# Dyn_MicSheet.net
KiCad netlist of a schematic drawn in Altium Designer
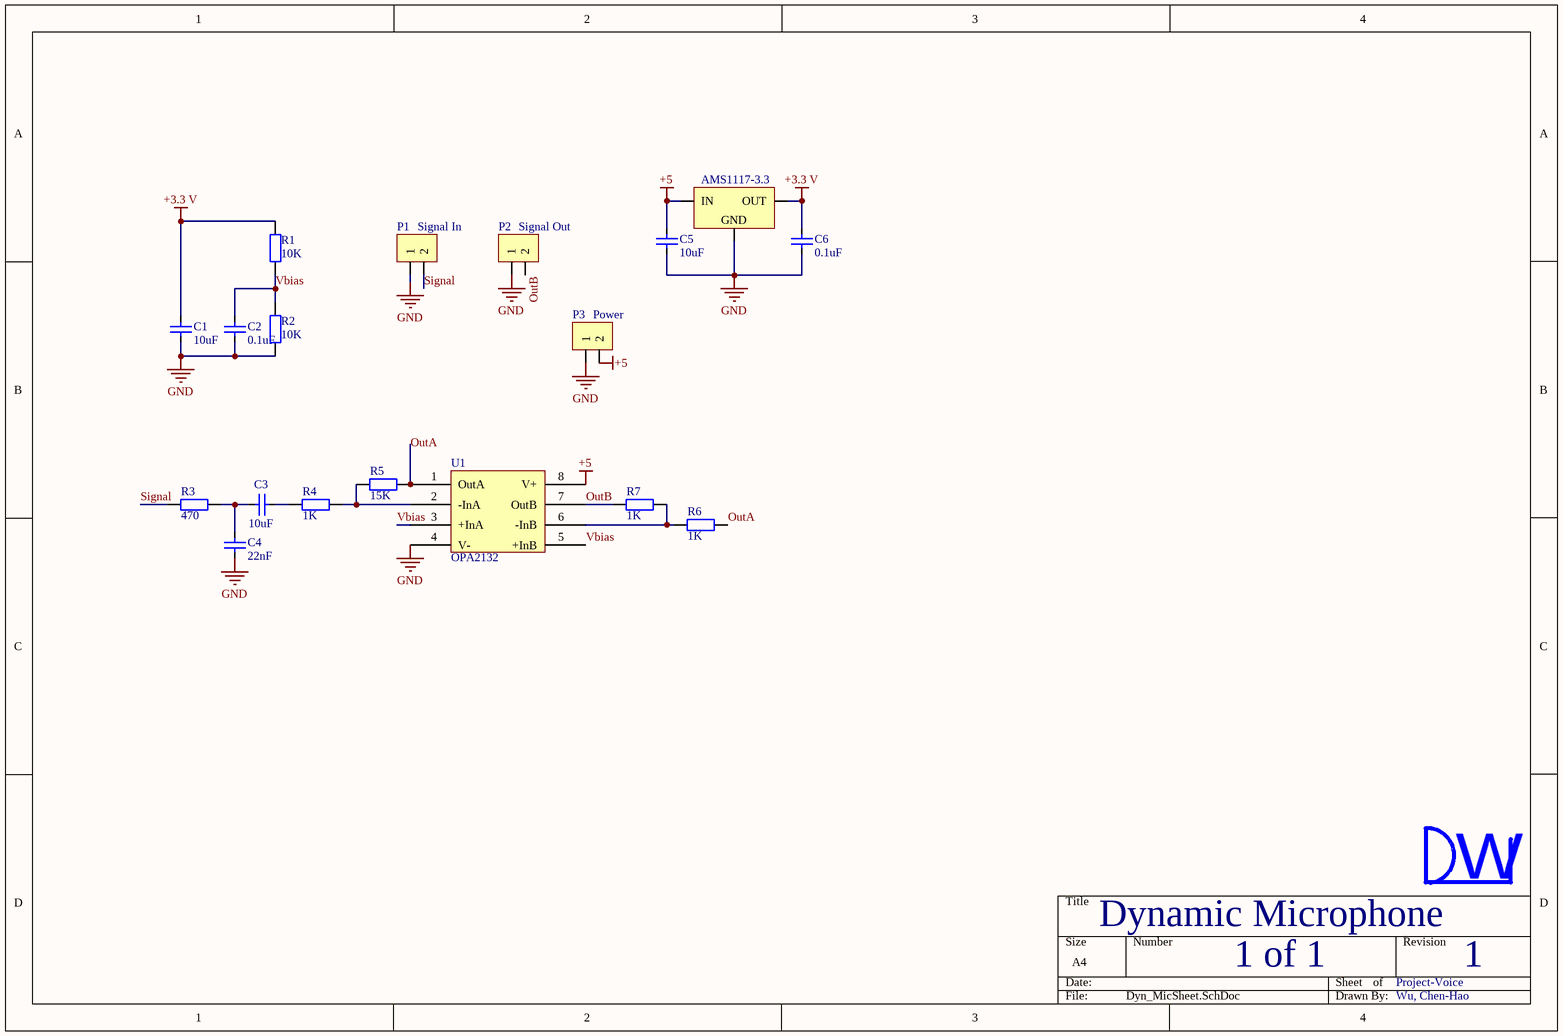
[diagram p0: Dyn_MicSheet.SchDoc]

(export (version "E")
  (design (tool "Eeschema 10.0.6"))
  (components
    (comp (ref "*") (value "DHW_MARK") (libsource (lib "SCH_Mark") (part "DHW_MARK")))
    (comp (ref "AMS1")
      (value "AMS1117-3.3")
      (footprint "PCB_IC:SOT223")
      (description "Power")
      (libsource (lib "SCH_IC") (part "AMS1117"))
    )
    (comp (ref "C1")
      (value "10uF")
      (footprint "PCB_Passive:CAP_0603")
      (description "Capacitor")
      (fields (field (name "Comment") "Cap_0603"))
      (libsource (lib "SCH_Passive") (part "Cap_0603"))
    )
    (comp (ref "C2")
      (value "0.1uF")
      (footprint "PCB_Passive:CAP_0603")
      (description "Capacitor")
      (fields (field (name "Comment") "Cap_0603"))
      (libsource (lib "SCH_Passive") (part "Cap_0603"))
    )
    (comp (ref "C3")
      (value "10uF")
      (footprint "PCB_Passive:CAP_0603")
      (description "Capacitor")
      (fields (field (name "Comment") "Cap_0603"))
      (libsource (lib "SCH_Passive") (part "Cap_0603"))
    )
    (comp (ref "C4")
      (value "22nF")
      (footprint "PCB_Passive:CAP_0603")
      (description "Capacitor")
      (fields (field (name "Comment") "Cap_0603"))
      (libsource (lib "SCH_Passive") (part "Cap_0603"))
    )
    (comp (ref "C5")
      (value "10uF")
      (footprint "PCB_Passive:CAP_0603")
      (description "Capacitor")
      (fields (field (name "Comment") "Cap_0603"))
      (libsource (lib "SCH_Passive") (part "Cap_0603"))
    )
    (comp (ref "C6")
      (value "0.1uF")
      (footprint "PCB_Passive:CAP_0603")
      (description "Capacitor")
      (fields (field (name "Comment") "Cap_0603"))
      (libsource (lib "SCH_Passive") (part "Cap_0603"))
    )
    (comp (ref "P1")
      (value "Signal In")
      (footprint "PCB_Connector:HDR1X2_180_2.54")
      (description "Header")
      (libsource (lib "SCH_Connector") (part "HDR1X2_180_2.54"))
    )
    (comp (ref "P2")
      (value "Signal Out")
      (footprint "PCB_Connector:HDR1X2_180_2.54")
      (description "Header")
      (libsource (lib "SCH_Connector") (part "HDR1X2_180_2.54"))
    )
    (comp (ref "P3")
      (value "Power")
      (footprint "PCB_Connector:HDR1X2_180_2.54")
      (description "Header")
      (libsource (lib "SCH_Connector") (part "HDR1X2_180_2.54"))
    )
    (comp (ref "R1")
      (value "10K")
      (footprint "PCB_Passive:RES_0603")
      (description "Resistor")
      (fields (field (name "Comment") "Res_0603"))
      (libsource (lib "") (part "Res_0603_1"))
    )
    (comp (ref "R2")
      (value "10K")
      (footprint "PCB_Passive:RES_0603")
      (description "Resistor")
      (fields (field (name "Comment") "Res_0603"))
      (libsource (lib "") (part "Res_0603_1"))
    )
    (comp (ref "R3")
      (value "470")
      (footprint "PCB_Passive:RES_0603")
      (description "Resistor")
      (fields (field (name "Comment") "Res_0603"))
      (libsource (lib "SCH_Passive") (part "Res_0603"))
    )
    (comp (ref "R4")
      (value "1K")
      (footprint "PCB_Passive:RES_0603")
      (description "Resistor")
      (fields (field (name "Comment") "Res_0603"))
      (libsource (lib "SCH_Passive") (part "Res_0603"))
    )
    (comp (ref "R5")
      (value "15K")
      (footprint "PCB_Passive:RES_0603")
      (description "Resistor")
      (fields (field (name "Comment") "Res_0603"))
      (libsource (lib "SCH_Passive") (part "Res_0603"))
    )
    (comp (ref "R6")
      (value "1K")
      (footprint "PCB_Passive:RES_0603")
      (description "Resistor")
      (fields (field (name "Comment") "Res_0603"))
      (libsource (lib "SCH_Passive") (part "Res_0603"))
    )
    (comp (ref "R7")
      (value "1K")
      (footprint "PCB_Passive:RES_0603")
      (description "Resistor")
      (fields (field (name "Comment") "Res_0603"))
      (libsource (lib "SCH_Passive") (part "Res_0603"))
    )
    (comp (ref "U1")
      (value "OPA2132")
      (footprint "DIP_8")
      (description "TI BB OPA2132 - 2 op amps IC")
      (libsource (lib "SCH_IC") (part "OPA2132"))
    )
  )
  (nets
    (net (code "1") (name "+3.3 V") (class "Default")
      (node (ref "AMS1") (pin "2") (pinfunction "OUT_2") (pintype "power_in"))
      (node (ref "C1") (pin "2") (pinfunction "2_2") (pintype "passive"))
      (node (ref "C6") (pin "2") (pinfunction "2_2") (pintype "passive"))
      (node (ref "R1") (pin "2") (pinfunction "2_2") (pintype "passive"))
    )
    (net (code "2") (name "+5") (class "Default")
      (node (ref "AMS1") (pin "3") (pinfunction "IN_3") (pintype "power_in"))
      (node (ref "C5") (pin "2") (pinfunction "2_2") (pintype "passive"))
      (node (ref "P3") (pin "2") (pinfunction "2_2") (pintype "passive"))
      (node (ref "U1") (pin "8") (pinfunction "V+_8") (pintype "passive"))
    )
    (net (code "3") (name "/OutA") (class "Default")
      (node (ref "R5") (pin "1") (pinfunction "1_1") (pintype "passive"))
      (node (ref "R6") (pin "1") (pinfunction "1_1") (pintype "passive"))
      (node (ref "U1") (pin "1") (pinfunction "OutA_1") (pintype "passive"))
    )
    (net (code "4") (name "/OutB") (class "Default")
      (node (ref "P2") (pin "2") (pinfunction "2_2") (pintype "passive"))
      (node (ref "R7") (pin "2") (pinfunction "2_2") (pintype "passive"))
      (node (ref "U1") (pin "7") (pinfunction "OutB_7") (pintype "passive"))
    )
    (net (code "5") (name "/Signal") (class "Default")
      (node (ref "P1") (pin "2") (pinfunction "2_2") (pintype "passive"))
      (node (ref "R3") (pin "2") (pinfunction "2_2") (pintype "passive"))
    )
    (net (code "6") (name "/Vbias") (class "Default")
      (node (ref "C2") (pin "2") (pinfunction "2_2") (pintype "passive"))
      (node (ref "R1") (pin "1") (pinfunction "1_1") (pintype "passive"))
      (node (ref "R2") (pin "2") (pinfunction "2_2") (pintype "passive"))
      (node (ref "U1") (pin "3") (pinfunction "+InA_3") (pintype "passive"))
      (node (ref "U1") (pin "5") (pinfunction "+InB_5") (pintype "passive"))
    )
    (net (code "7") (name "GND") (class "Default")
      (node (ref "AMS1") (pin "1") (pinfunction "GND_1") (pintype "power_in"))
      (node (ref "C1") (pin "1") (pinfunction "1_1") (pintype "passive"))
      (node (ref "C2") (pin "1") (pinfunction "1_1") (pintype "passive"))
      (node (ref "C4") (pin "1") (pinfunction "1_1") (pintype "passive"))
      (node (ref "C5") (pin "1") (pinfunction "1_1") (pintype "passive"))
      (node (ref "C6") (pin "1") (pinfunction "1_1") (pintype "passive"))
      (node (ref "P1") (pin "1") (pinfunction "1_1") (pintype "passive"))
      (node (ref "P2") (pin "1") (pinfunction "1_1") (pintype "passive"))
      (node (ref "P3") (pin "1") (pinfunction "1_1") (pintype "passive"))
      (node (ref "R2") (pin "1") (pinfunction "1_1") (pintype "passive"))
      (node (ref "U1") (pin "4") (pinfunction "V-_4") (pintype "passive"))
    )
    (net (code "8") (name "Net-(C3-Pad1)") (class "Default")
      (node (ref "C3") (pin "1") (pinfunction "1_1") (pintype "passive"))
      (node (ref "R4") (pin "2") (pinfunction "2_2") (pintype "passive"))
    )
    (net (code "9") (name "Net-(C3-Pad2)") (class "Default")
      (node (ref "C3") (pin "2") (pinfunction "2_2") (pintype "passive"))
      (node (ref "C4") (pin "2") (pinfunction "2_2") (pintype "passive"))
      (node (ref "R3") (pin "1") (pinfunction "1_1") (pintype "passive"))
    )
    (net (code "10") (name "Net-(U1--InA)") (class "Default")
      (node (ref "R4") (pin "1") (pinfunction "1_1") (pintype "passive"))
      (node (ref "R5") (pin "2") (pinfunction "2_2") (pintype "passive"))
      (node (ref "U1") (pin "2") (pinfunction "-InA_2") (pintype "passive"))
    )
    (net (code "11") (name "Net-(U1--InB)") (class "Default")
      (node (ref "R6") (pin "2") (pinfunction "2_2") (pintype "passive"))
      (node (ref "R7") (pin "1") (pinfunction "1_1") (pintype "passive"))
      (node (ref "U1") (pin "6") (pinfunction "-InB_6") (pintype "passive"))
    )
  )
)
